# master_jorge3.net
KiCad netlist of a schematic drawn in EAGLE
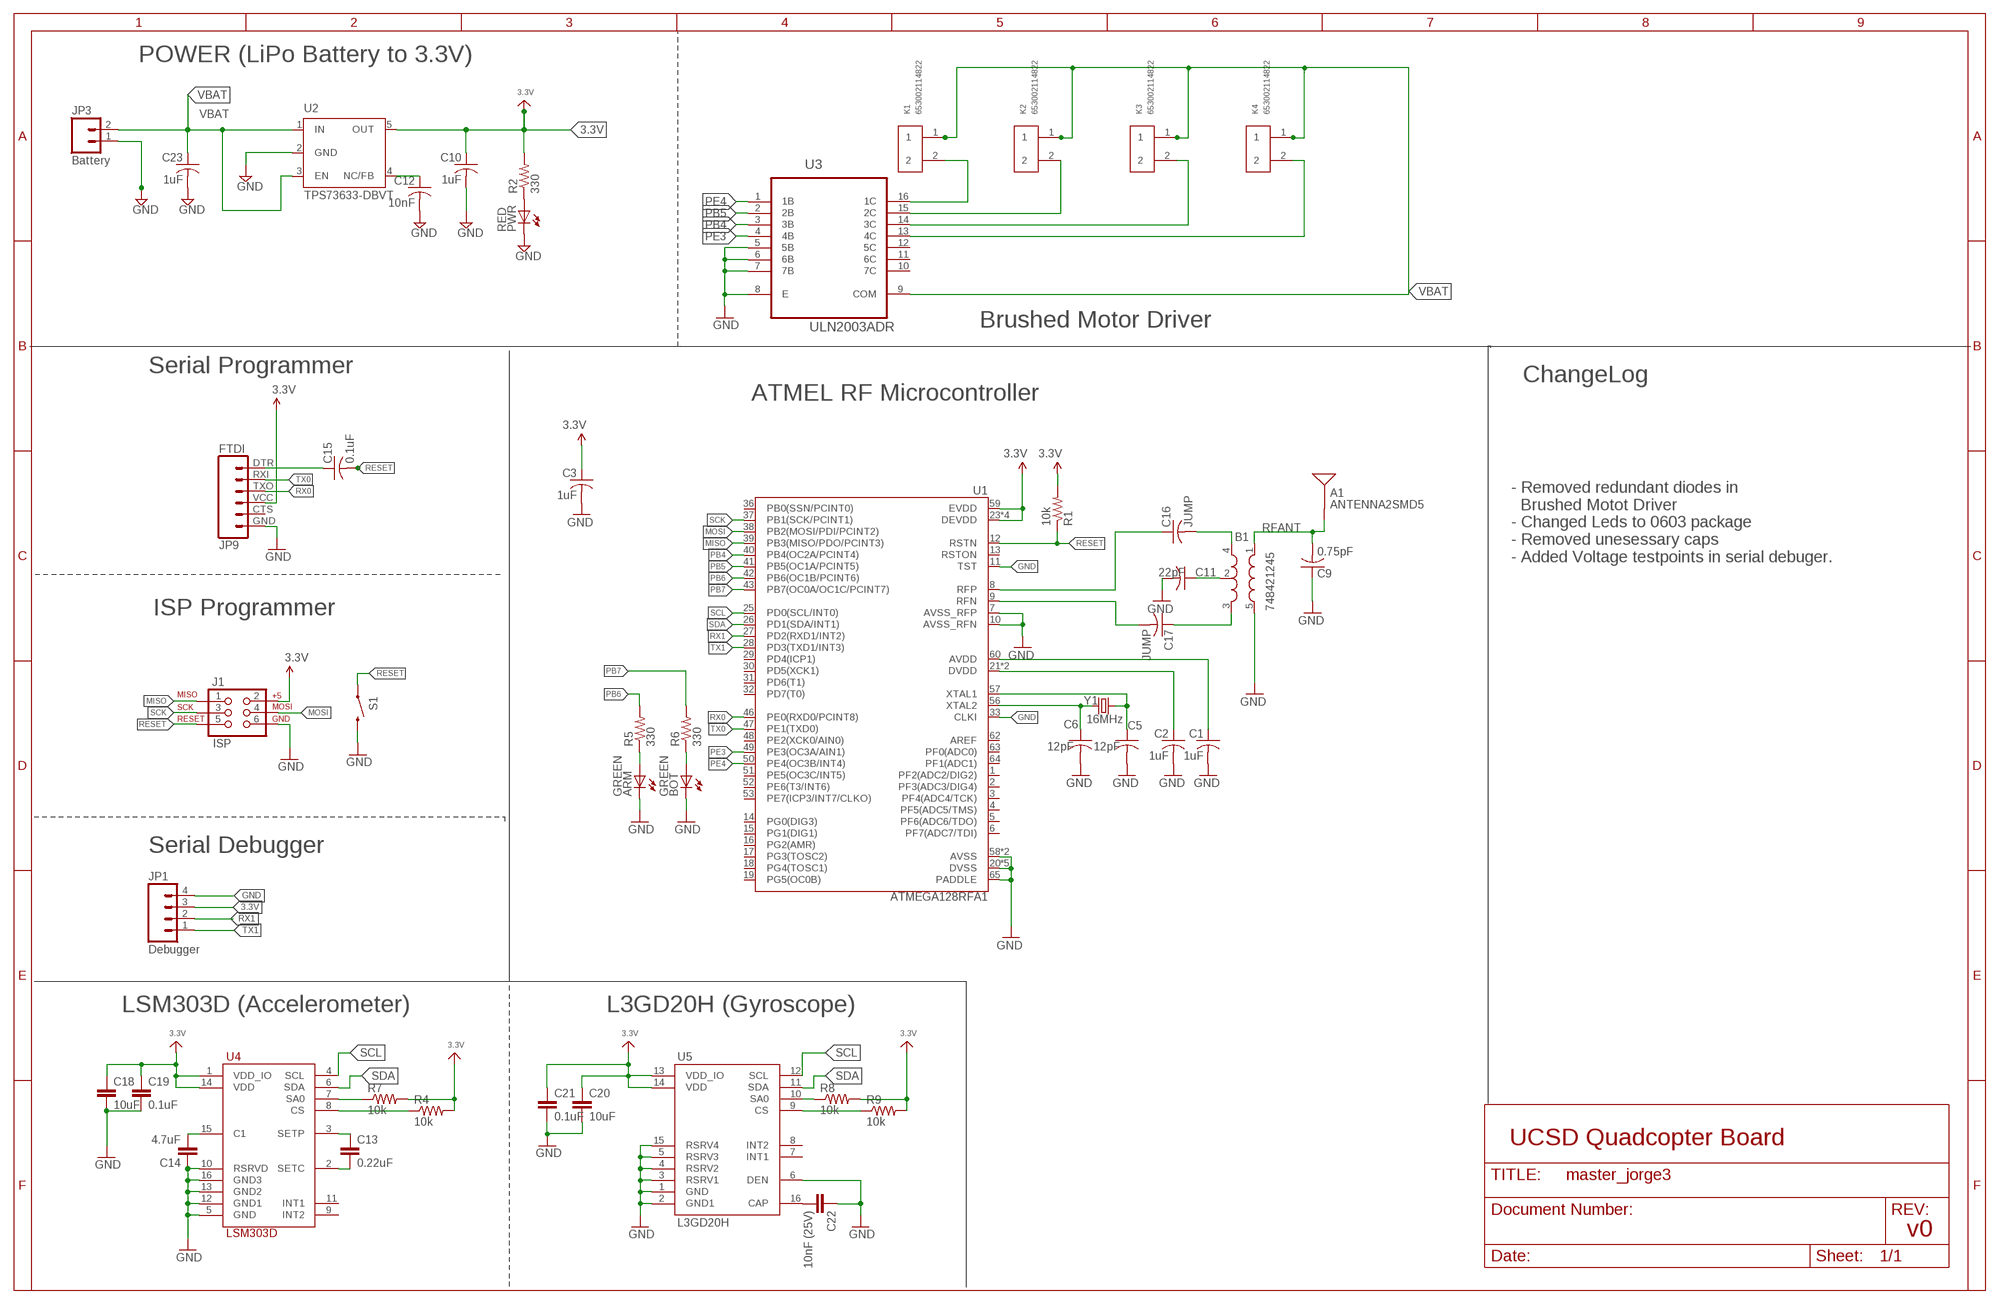
[diagram p0: schematic, sheet 1]

(export (version "E")
  (design (tool "Eeschema 10.0.6"))
  (components
    (comp (ref "A1")
      (value "ANTENNA2SMD5")
      (footprint "eagle-import:ANTENNA-CHIP5")
      (libsource (lib "eagle-import") (part "ANTENNA2SMD5"))
    )
    (comp (ref "ARM")
      (value "GREEN")
      (footprint "eagle-import:CHIP-LED0805")
      (libsource (lib "eagle-import") (part "LEDCHIP-LED0805"))
    )
    (comp (ref "B1")
      (value "748421245")
      (footprint "eagle-import:BALUN")
      (libsource (lib "eagle-import") (part "BALUN0805"))
    )
    (comp (ref "BOT")
      (value "GREEN")
      (footprint "eagle-import:CHIP-LED0805")
      (libsource (lib "eagle-import") (part "LEDCHIP-LED0805"))
    )
    (comp (ref "C1")
      (value "1uF")
      (footprint "eagle-import:C0805")
      (libsource (lib "eagle-import") (part "C-USC0805"))
    )
    (comp (ref "C2")
      (value "1uF")
      (footprint "eagle-import:C0805")
      (libsource (lib "eagle-import") (part "C-USC0805"))
    )
    (comp (ref "C3")
      (value "1uF")
      (footprint "eagle-import:C0805")
      (libsource (lib "eagle-import") (part "C-USC0805"))
    )
    (comp (ref "C5")
      (value "12pF")
      (footprint "eagle-import:C0805")
      (libsource (lib "eagle-import") (part "C-USC0805"))
    )
    (comp (ref "C6")
      (value "12pF")
      (footprint "eagle-import:C0805")
      (libsource (lib "eagle-import") (part "C-USC0805"))
    )
    (comp (ref "C9")
      (value "0.75pF")
      (footprint "eagle-import:C0805")
      (libsource (lib "eagle-import") (part "C-USC0805"))
    )
    (comp (ref "C10")
      (value "1uF")
      (footprint "eagle-import:C0805")
      (libsource (lib "eagle-import") (part "C-USC0805"))
    )
    (comp (ref "C11")
      (value "22pF")
      (footprint "eagle-import:C0805")
      (libsource (lib "eagle-import") (part "C-USC0805"))
    )
    (comp (ref "C12")
      (value "10nF")
      (footprint "eagle-import:C0805")
      (libsource (lib "eagle-import") (part "C-USC0805"))
    )
    (comp (ref "C13")
      (value "0.22uF")
      (footprint "eagle-import:0805")
      (libsource (lib "eagle-import") (part "CAP0805"))
    )
    (comp (ref "C14")
      (value "4.7uF")
      (footprint "eagle-import:0805")
      (libsource (lib "eagle-import") (part "CAP0805"))
    )
    (comp (ref "C15")
      (value "0.1uF")
      (footprint "eagle-import:C0805")
      (libsource (lib "eagle-import") (part "C-USC0805"))
    )
    (comp (ref "C16")
      (value "JUMP")
      (footprint "eagle-import:C0805")
      (libsource (lib "eagle-import") (part "C-USC0805"))
    )
    (comp (ref "C17")
      (value "JUMP")
      (footprint "eagle-import:C0805")
      (libsource (lib "eagle-import") (part "C-USC0805"))
    )
    (comp (ref "C18")
      (value "10uF")
      (footprint "eagle-import:0805")
      (libsource (lib "eagle-import") (part "CAP0805"))
    )
    (comp (ref "C19")
      (value "0.1uF")
      (footprint "eagle-import:0805")
      (libsource (lib "eagle-import") (part "CAP0805"))
    )
    (comp (ref "C20")
      (value "10uF")
      (footprint "eagle-import:0805")
      (libsource (lib "eagle-import") (part "CAP0805"))
    )
    (comp (ref "C21")
      (value "0.1uF")
      (footprint "eagle-import:0805")
      (libsource (lib "eagle-import") (part "CAP0805"))
    )
    (comp (ref "C22")
      (value "10nF (25V)")
      (footprint "eagle-import:0805")
      (libsource (lib "eagle-import") (part "CAP0805"))
    )
    (comp (ref "C23")
      (value "1uF")
      (footprint "eagle-import:C0805")
      (libsource (lib "eagle-import") (part "C-USC0805"))
    )
    (comp (ref "J1")
      (value "ISP")
      (footprint "eagle-import:2X3-NS")
      (libsource (lib "eagle-import") (part "AVR_SPI_PRG_6NS"))
    )
    (comp (ref "JP1")
      (value "Debugger")
      (footprint "eagle-import:1X04")
      (libsource (lib "eagle-import") (part "M04PTH"))
    )
    (comp (ref "JP3")
      (value "Battery")
      (footprint "eagle-import:1X02")
      (libsource (lib "eagle-import") (part "M02PTH"))
    )
    (comp (ref "JP9")
      (value "FTDI")
      (footprint "eagle-import:FTDI_BASIC")
      (libsource (lib "eagle-import") (part "FTDI_BASICPTH"))
    )
    (comp (ref "K1")
      (value "653002114822")
      (footprint "eagle-import:653002114822")
      (libsource (lib "eagle-import") (part "653002114822"))
    )
    (comp (ref "K2")
      (value "653002114822")
      (footprint "eagle-import:653002114822")
      (libsource (lib "eagle-import") (part "653002114822"))
    )
    (comp (ref "K3")
      (value "653002114822")
      (footprint "eagle-import:653002114822")
      (libsource (lib "eagle-import") (part "653002114822"))
    )
    (comp (ref "K4")
      (value "653002114822")
      (footprint "eagle-import:653002114822")
      (libsource (lib "eagle-import") (part "653002114822"))
    )
    (comp (ref "PWR")
      (value "RED")
      (footprint "eagle-import:CHIP-LED0805")
      (libsource (lib "eagle-import") (part "LEDCHIP-LED0805"))
    )
    (comp (ref "R1")
      (value "10k")
      (footprint "eagle-import:R0805")
      (libsource (lib "eagle-import") (part "R-US_R0805"))
    )
    (comp (ref "R2")
      (value "330")
      (footprint "eagle-import:R0805")
      (libsource (lib "eagle-import") (part "R-US_R0805"))
    )
    (comp (ref "R4")
      (value "10k")
      (footprint "eagle-import:0805")
      (libsource (lib "eagle-import") (part "RESISTOR0805-RES"))
    )
    (comp (ref "R5")
      (value "330")
      (footprint "eagle-import:R0805")
      (libsource (lib "eagle-import") (part "R-US_R0805"))
    )
    (comp (ref "R6")
      (value "330")
      (footprint "eagle-import:R0805")
      (libsource (lib "eagle-import") (part "R-US_R0805"))
    )
    (comp (ref "R7")
      (value "10k")
      (footprint "eagle-import:0805")
      (libsource (lib "eagle-import") (part "RESISTOR0805-RES"))
    )
    (comp (ref "R8")
      (value "10k")
      (footprint "eagle-import:0805")
      (libsource (lib "eagle-import") (part "RESISTOR0805-RES"))
    )
    (comp (ref "R9")
      (value "10k")
      (footprint "eagle-import:0805")
      (libsource (lib "eagle-import") (part "RESISTOR0805-RES"))
    )
    (comp (ref "S1")
      (value "SWITCH-MOMENTARY-2SMD")
      (footprint "eagle-import:TACTILE_SWITCH_SMD")
      (libsource (lib "eagle-import") (part "SWITCH-MOMENTARY-2SMD"))
    )
    (comp (ref "U1")
      (value "ATMEGA128RFA1")
      (footprint "eagle-import:QFN-64")
      (libsource (lib "eagle-import") (part "ATMEGA128RFA1"))
    )
    (comp (ref "U2")
      (value "TPS73633-DBVT")
      (footprint "eagle-import:SOT23-DBV")
      (libsource (lib "eagle-import") (part "TPS73633-DBVT"))
    )
    (comp (ref "U3")
      (value "ULN2003ADR")
      (footprint "eagle-import:SOIC127P600X175-16N")
      (libsource (lib "eagle-import") (part "ULN2003ADR"))
    )
    (comp (ref "U4")
      (value "LSM303D")
      (footprint "eagle-import:LGA16_3X3MM")
      (libsource (lib "eagle-import") (part "LSM303D"))
    )
    (comp (ref "U5")
      (value "L3GD20H")
      (footprint "eagle-import:LGA16_3X3MM")
      (libsource (lib "eagle-import") (part "L3GD20H"))
    )
    (comp (ref "Y1")
      (value "16MHz")
      (footprint "eagle-import:CRYSTAL-SMD-5X3")
      (libsource (lib "eagle-import") (part "CRYSTAL5X3"))
    )
  )
  (nets
    (net (code "1") (name "/RFANT") (class "Default")
      (node (ref "A1") (pin "FEED") (pinfunction "SIGNAL_FEED") (pintype "bidirectional"))
      (node (ref "B1") (pin "1") (pinfunction "IN_1") (pintype "bidirectional"))
      (node (ref "C9") (pin "2") (pinfunction "2_2") (pintype "passive"))
    )
    (net (code "2") (name "3.3V") (class "Default")
      (node (ref "C10") (pin "1") (pinfunction "1_1") (pintype "passive"))
      (node (ref "C18") (pin "1") (pinfunction "1_1") (pintype "passive"))
      (node (ref "C19") (pin "1") (pinfunction "1_1") (pintype "passive"))
      (node (ref "C20") (pin "1") (pinfunction "1_1") (pintype "passive"))
      (node (ref "C21") (pin "1") (pinfunction "1_1") (pintype "passive"))
      (node (ref "C3") (pin "1") (pinfunction "1_1") (pintype "passive"))
      (node (ref "J1") (pin "2") (pinfunction "2_2") (pintype "passive"))
      (node (ref "JP1") (pin "3") (pinfunction "3_3") (pintype "passive"))
      (node (ref "JP9") (pin "VCC") (pinfunction "4_VCC") (pintype "passive"))
      (node (ref "R1") (pin "2") (pinfunction "2_2") (pintype "passive"))
      (node (ref "R2") (pin "2") (pinfunction "2_2") (pintype "passive"))
      (node (ref "R4") (pin "2") (pinfunction "2_2") (pintype "passive"))
      (node (ref "R7") (pin "2") (pinfunction "2_2") (pintype "passive"))
      (node (ref "R8") (pin "2") (pinfunction "2_2") (pintype "passive"))
      (node (ref "R9") (pin "2") (pinfunction "2_2") (pintype "passive"))
      (node (ref "U1") (pin "23") (pinfunction "DEVDD_23") (pintype "bidirectional"))
      (node (ref "U1") (pin "34") (pinfunction "DEVDD_34") (pintype "bidirectional"))
      (node (ref "U1") (pin "44") (pinfunction "DEVDD_44") (pintype "bidirectional"))
      (node (ref "U1") (pin "54") (pinfunction "DEVDD_54") (pintype "bidirectional"))
      (node (ref "U1") (pin "59") (pinfunction "EVDD_59") (pintype "bidirectional"))
      (node (ref "U2") (pin "5") (pinfunction "OUT_5") (pintype "passive"))
      (node (ref "U4") (pin "1") (pinfunction "VDD_IO_1") (pintype "bidirectional"))
      (node (ref "U4") (pin "14") (pinfunction "VDD_14") (pintype "bidirectional"))
      (node (ref "U5") (pin "13") (pinfunction "VDD_IO_13") (pintype "bidirectional"))
      (node (ref "U5") (pin "14") (pinfunction "VDD_14") (pintype "bidirectional"))
    )
    (net (code "3") (name "GND") (class "Default")
      (node (ref "ARM") (pin "C") (pinfunction "C_C") (pintype "passive"))
      (node (ref "B1") (pin "5") (pinfunction "GND_5") (pintype "bidirectional"))
      (node (ref "BOT") (pin "C") (pinfunction "C_C") (pintype "passive"))
      (node (ref "C1") (pin "2") (pinfunction "2_2") (pintype "passive"))
      (node (ref "C10") (pin "2") (pinfunction "2_2") (pintype "passive"))
      (node (ref "C11") (pin "2") (pinfunction "2_2") (pintype "passive"))
      (node (ref "C12") (pin "2") (pinfunction "2_2") (pintype "passive"))
      (node (ref "C14") (pin "1") (pinfunction "1_1") (pintype "passive"))
      (node (ref "C18") (pin "2") (pinfunction "2_2") (pintype "passive"))
      (node (ref "C19") (pin "2") (pinfunction "2_2") (pintype "passive"))
      (node (ref "C2") (pin "2") (pinfunction "2_2") (pintype "passive"))
      (node (ref "C20") (pin "2") (pinfunction "2_2") (pintype "passive"))
      (node (ref "C21") (pin "2") (pinfunction "2_2") (pintype "passive"))
      (node (ref "C22") (pin "1") (pinfunction "1_1") (pintype "passive"))
      (node (ref "C23") (pin "2") (pinfunction "2_2") (pintype "passive"))
      (node (ref "C3") (pin "2") (pinfunction "2_2") (pintype "passive"))
      (node (ref "C5") (pin "2") (pinfunction "2_2") (pintype "passive"))
      (node (ref "C6") (pin "2") (pinfunction "2_2") (pintype "passive"))
      (node (ref "C9") (pin "1") (pinfunction "1_1") (pintype "passive"))
      (node (ref "J1") (pin "6") (pinfunction "6_6") (pintype "passive"))
      (node (ref "JP1") (pin "4") (pinfunction "4_4") (pintype "passive"))
      (node (ref "JP3") (pin "1") (pinfunction "1_1") (pintype "passive"))
      (node (ref "JP9") (pin "GND") (pinfunction "6_GND") (pintype "passive"))
      (node (ref "PWR") (pin "C") (pinfunction "C_C") (pintype "passive"))
      (node (ref "S1") (pin "3") (pinfunction "2_3") (pintype "passive"))
      (node (ref "U1") (pin "10") (pinfunction "AVSS_RFN_10") (pintype "bidirectional"))
      (node (ref "U1") (pin "11") (pinfunction "TST_11") (pintype "bidirectional"))
      (node (ref "U1") (pin "20") (pinfunction "DVSS_20") (pintype "bidirectional"))
      (node (ref "U1") (pin "24") (pinfunction "DVSS_24") (pintype "bidirectional"))
      (node (ref "U1") (pin "33") (pinfunction "CLKI_33") (pintype "bidirectional"))
      (node (ref "U1") (pin "35") (pinfunction "DVSS_35") (pintype "bidirectional"))
      (node (ref "U1") (pin "45") (pinfunction "DVSS_45") (pintype "bidirectional"))
      (node (ref "U1") (pin "55") (pinfunction "DVSS_55") (pintype "bidirectional"))
      (node (ref "U1") (pin "58") (pinfunction "AVSS_58") (pintype "bidirectional"))
      (node (ref "U1") (pin "61") (pinfunction "AVSS_61") (pintype "bidirectional"))
      (node (ref "U1") (pin "65") (pinfunction "PADDLE_65") (pintype "bidirectional"))
      (node (ref "U1") (pin "7") (pinfunction "AVSS_RFP_7") (pintype "bidirectional"))
      (node (ref "U2") (pin "2") (pinfunction "GND_2") (pintype "input"))
      (node (ref "U3") (pin "5") (pinfunction "5B_5") (pintype "input"))
      (node (ref "U3") (pin "6") (pinfunction "6B_6") (pintype "input"))
      (node (ref "U3") (pin "7") (pinfunction "7B_7") (pintype "input"))
      (node (ref "U3") (pin "8") (pinfunction "E_8") (pintype "input"))
      (node (ref "U4") (pin "10") (pinfunction "RSRVD_10") (pintype "bidirectional"))
      (node (ref "U4") (pin "12") (pinfunction "GND1_12") (pintype "bidirectional"))
      (node (ref "U4") (pin "13") (pinfunction "GND2_13") (pintype "bidirectional"))
      (node (ref "U4") (pin "16") (pinfunction "GND3_16") (pintype "bidirectional"))
      (node (ref "U4") (pin "5") (pinfunction "GND_5") (pintype "bidirectional"))
      (node (ref "U5") (pin "1") (pinfunction "GND_1") (pintype "bidirectional"))
      (node (ref "U5") (pin "15") (pinfunction "RSRV4_15") (pintype "bidirectional"))
      (node (ref "U5") (pin "2") (pinfunction "GND1_2") (pintype "bidirectional"))
      (node (ref "U5") (pin "3") (pinfunction "RSRV1_3") (pintype "bidirectional"))
      (node (ref "U5") (pin "4") (pinfunction "RSRV2_4") (pintype "bidirectional"))
      (node (ref "U5") (pin "5") (pinfunction "RSRV3_5") (pintype "bidirectional"))
      (node (ref "U5") (pin "6") (pinfunction "DEN_6") (pintype "bidirectional"))
    )
    (net (code "4") (name "MISO") (class "Default")
      (node (ref "J1") (pin "1") (pinfunction "1_1") (pintype "passive"))
      (node (ref "U1") (pin "39") (pinfunction "PB3(MISO/PDO/PCINT3)_39") (pintype "bidirectional"))
    )
    (net (code "5") (name "MOSI") (class "Default")
      (node (ref "J1") (pin "4") (pinfunction "4_4") (pintype "passive"))
      (node (ref "U1") (pin "38") (pinfunction "PB2(MOSI/PDI/PCINT2)_38") (pintype "bidirectional"))
    )
    (net (code "6") (name "Net-(ARM-PadA)") (class "Default")
      (node (ref "ARM") (pin "A") (pinfunction "A_A") (pintype "passive"))
      (node (ref "R5") (pin "1") (pinfunction "1_1") (pintype "passive"))
    )
    (net (code "7") (name "Net-(B1-GND-Pad2)") (class "Default")
      (node (ref "B1") (pin "2") (pinfunction "GND_2") (pintype "bidirectional"))
      (node (ref "C11") (pin "1") (pinfunction "1_1") (pintype "passive"))
    )
    (net (code "8") (name "Net-(B1-OUT1)") (class "Default")
      (node (ref "B1") (pin "4") (pinfunction "OUT1_4") (pintype "bidirectional"))
      (node (ref "C16") (pin "2") (pinfunction "2_2") (pintype "passive"))
    )
    (net (code "9") (name "Net-(B1-OUT2)") (class "Default")
      (node (ref "B1") (pin "3") (pinfunction "OUT2_3") (pintype "bidirectional"))
      (node (ref "C17") (pin "1") (pinfunction "1_1") (pintype "passive"))
    )
    (net (code "10") (name "Net-(BOT-PadA)") (class "Default")
      (node (ref "BOT") (pin "A") (pinfunction "A_A") (pintype "passive"))
      (node (ref "R6") (pin "1") (pinfunction "1_1") (pintype "passive"))
    )
    (net (code "11") (name "Net-(C2-Pad1)") (class "Default")
      (node (ref "C2") (pin "1") (pinfunction "1_1") (pintype "passive"))
      (node (ref "U1") (pin "21") (pinfunction "DVDD_21") (pintype "bidirectional"))
      (node (ref "U1") (pin "22") (pinfunction "DVDD_22") (pintype "bidirectional"))
    )
    (net (code "12") (name "Net-(JP9-1)") (class "Default")
      (node (ref "C15") (pin "1") (pinfunction "1_1") (pintype "passive"))
      (node (ref "JP9") (pin "DTR") (pinfunction "1_DTR") (pintype "passive"))
    )
    (net (code "13") (name "Net-(PWR-PadA)") (class "Default")
      (node (ref "PWR") (pin "A") (pinfunction "A_A") (pintype "passive"))
      (node (ref "R2") (pin "1") (pinfunction "1_1") (pintype "passive"))
    )
    (net (code "14") (name "Net-(U1-AVDD)") (class "Default")
      (node (ref "C1") (pin "1") (pinfunction "1_1") (pintype "passive"))
      (node (ref "U1") (pin "60") (pinfunction "AVDD_60") (pintype "bidirectional"))
    )
    (net (code "15") (name "Net-(U1-RFN)") (class "Default")
      (node (ref "C17") (pin "2") (pinfunction "2_2") (pintype "passive"))
      (node (ref "U1") (pin "9") (pinfunction "RFN_9") (pintype "bidirectional"))
    )
    (net (code "16") (name "Net-(U1-RFP)") (class "Default")
      (node (ref "C16") (pin "1") (pinfunction "1_1") (pintype "passive"))
      (node (ref "U1") (pin "8") (pinfunction "RFP_8") (pintype "bidirectional"))
    )
    (net (code "17") (name "Net-(U1-XTAL1)") (class "Default")
      (node (ref "C5") (pin "1") (pinfunction "1_1") (pintype "passive"))
      (node (ref "U1") (pin "57") (pinfunction "XTAL1_57") (pintype "bidirectional"))
      (node (ref "Y1") (pin "3") (pinfunction "2_3") (pintype "passive"))
    )
    (net (code "18") (name "Net-(U1-XTAL2)") (class "Default")
      (node (ref "C6") (pin "1") (pinfunction "1_1") (pintype "passive"))
      (node (ref "U1") (pin "56") (pinfunction "XTAL2_56") (pintype "bidirectional"))
      (node (ref "Y1") (pin "1") (pinfunction "1_1") (pintype "passive"))
    )
    (net (code "19") (name "Net-(U2-NC{slash}FB)") (class "Default")
      (node (ref "C12") (pin "1") (pinfunction "1_1") (pintype "passive"))
      (node (ref "U2") (pin "4") (pinfunction "NC/FB_4") (pintype "passive"))
    )
    (net (code "20") (name "Net-(U3-1C)") (class "Default")
      (node (ref "K1") (pin "2") (pinfunction "2_2") (pintype "bidirectional"))
      (node (ref "U3") (pin "16") (pinfunction "1C_16") (pintype "output"))
    )
    (net (code "21") (name "Net-(U3-2C)") (class "Default")
      (node (ref "K2") (pin "2") (pinfunction "2_2") (pintype "bidirectional"))
      (node (ref "U3") (pin "15") (pinfunction "2C_15") (pintype "output"))
    )
    (net (code "22") (name "Net-(U3-3C)") (class "Default")
      (node (ref "K3") (pin "2") (pinfunction "2_2") (pintype "bidirectional"))
      (node (ref "U3") (pin "14") (pinfunction "3C_14") (pintype "output"))
    )
    (net (code "23") (name "Net-(U3-4C)") (class "Default")
      (node (ref "K4") (pin "2") (pinfunction "2_2") (pintype "bidirectional"))
      (node (ref "U3") (pin "13") (pinfunction "4C_13") (pintype "output"))
    )
    (net (code "24") (name "Net-(U4-C1)") (class "Default")
      (node (ref "C14") (pin "2") (pinfunction "2_2") (pintype "passive"))
      (node (ref "U4") (pin "15") (pinfunction "C1_15") (pintype "bidirectional"))
    )
    (net (code "25") (name "Net-(U4-CS)") (class "Default")
      (node (ref "R4") (pin "1") (pinfunction "1_1") (pintype "passive"))
      (node (ref "U4") (pin "8") (pinfunction "CS_8") (pintype "bidirectional"))
    )
    (net (code "26") (name "Net-(U4-SA0)") (class "Default")
      (node (ref "R7") (pin "1") (pinfunction "1_1") (pintype "passive"))
      (node (ref "U4") (pin "7") (pinfunction "SA0_7") (pintype "bidirectional"))
    )
    (net (code "27") (name "Net-(U4-SETC)") (class "Default")
      (node (ref "C13") (pin "2") (pinfunction "2_2") (pintype "passive"))
      (node (ref "U4") (pin "2") (pinfunction "SETC_2") (pintype "bidirectional"))
    )
    (net (code "28") (name "Net-(U4-SETP)") (class "Default")
      (node (ref "C13") (pin "1") (pinfunction "1_1") (pintype "passive"))
      (node (ref "U4") (pin "3") (pinfunction "SETP_3") (pintype "bidirectional"))
    )
    (net (code "29") (name "Net-(U5-CAP)") (class "Default")
      (node (ref "C22") (pin "2") (pinfunction "2_2") (pintype "passive"))
      (node (ref "U5") (pin "16") (pinfunction "CAP_16") (pintype "bidirectional"))
    )
    (net (code "30") (name "Net-(U5-CS)") (class "Default")
      (node (ref "R9") (pin "1") (pinfunction "1_1") (pintype "passive"))
      (node (ref "U5") (pin "9") (pinfunction "CS_9") (pintype "bidirectional"))
    )
    (net (code "31") (name "Net-(U5-SA0)") (class "Default")
      (node (ref "R8") (pin "1") (pinfunction "1_1") (pintype "passive"))
      (node (ref "U5") (pin "10") (pinfunction "SA0_10") (pintype "bidirectional"))
    )
    (net (code "32") (name "PB4") (class "Default")
      (node (ref "U1") (pin "40") (pinfunction "PB4(OC2A/PCINT4)_40") (pintype "bidirectional"))
      (node (ref "U3") (pin "3") (pinfunction "3B_3") (pintype "input"))
    )
    (net (code "33") (name "PB5") (class "Default")
      (node (ref "U1") (pin "41") (pinfunction "PB5(OC1A/PCINT5)_41") (pintype "bidirectional"))
      (node (ref "U3") (pin "2") (pinfunction "2B_2") (pintype "input"))
    )
    (net (code "34") (name "PB6") (class "Default")
      (node (ref "R5") (pin "2") (pinfunction "2_2") (pintype "passive"))
      (node (ref "U1") (pin "42") (pinfunction "PB6(OC1B/PCINT6)_42") (pintype "bidirectional"))
    )
    (net (code "35") (name "PB7") (class "Default")
      (node (ref "R6") (pin "2") (pinfunction "2_2") (pintype "passive"))
      (node (ref "U1") (pin "43") (pinfunction "PB7(OC0A/OC1C/PCINT7)_43") (pintype "bidirectional"))
    )
    (net (code "36") (name "PE3") (class "Default")
      (node (ref "U1") (pin "49") (pinfunction "PE3(OC3A/AIN1)_49") (pintype "bidirectional"))
      (node (ref "U3") (pin "4") (pinfunction "4B_4") (pintype "input"))
    )
    (net (code "37") (name "PE4") (class "Default")
      (node (ref "U1") (pin "50") (pinfunction "PE4(OC3B/INT4)_50") (pintype "bidirectional"))
      (node (ref "U3") (pin "1") (pinfunction "1B_1") (pintype "input"))
    )
    (net (code "38") (name "RESET") (class "Default")
      (node (ref "C15") (pin "2") (pinfunction "2_2") (pintype "passive"))
      (node (ref "J1") (pin "5") (pinfunction "5_5") (pintype "passive"))
      (node (ref "R1") (pin "1") (pinfunction "1_1") (pintype "passive"))
      (node (ref "S1") (pin "1") (pinfunction "1_1") (pintype "passive"))
      (node (ref "U1") (pin "12") (pinfunction "RSTN_12") (pintype "bidirectional"))
    )
    (net (code "39") (name "RX0") (class "Default")
      (node (ref "JP9") (pin "TXO") (pinfunction "3_TXO") (pintype "passive"))
      (node (ref "U1") (pin "46") (pinfunction "PE0(RXD0/PCINT8)_46") (pintype "bidirectional"))
    )
    (net (code "40") (name "RX1") (class "Default")
      (node (ref "JP1") (pin "2") (pinfunction "2_2") (pintype "passive"))
      (node (ref "U1") (pin "27") (pinfunction "PD2(RXD1/INT2)_27") (pintype "bidirectional"))
    )
    (net (code "41") (name "SCK") (class "Default")
      (node (ref "J1") (pin "3") (pinfunction "3_3") (pintype "passive"))
      (node (ref "U1") (pin "37") (pinfunction "PB1(SCK/PCINT1)_37") (pintype "bidirectional"))
    )
    (net (code "42") (name "SCL") (class "Default")
      (node (ref "U1") (pin "25") (pinfunction "PD0(SCL/INT0)_25") (pintype "bidirectional"))
      (node (ref "U4") (pin "4") (pinfunction "SCL_4") (pintype "bidirectional"))
      (node (ref "U5") (pin "12") (pinfunction "SCL_12") (pintype "bidirectional"))
    )
    (net (code "43") (name "SDA") (class "Default")
      (node (ref "U1") (pin "26") (pinfunction "PD1(SDA/INT1)_26") (pintype "bidirectional"))
      (node (ref "U4") (pin "6") (pinfunction "SDA_6") (pintype "bidirectional"))
      (node (ref "U5") (pin "11") (pinfunction "SDA_11") (pintype "bidirectional"))
    )
    (net (code "44") (name "TX0") (class "Default")
      (node (ref "JP9") (pin "RXI") (pinfunction "2_RXI") (pintype "passive"))
      (node (ref "U1") (pin "47") (pinfunction "PE1(TXD0)_47") (pintype "bidirectional"))
    )
    (net (code "45") (name "TX1") (class "Default")
      (node (ref "JP1") (pin "1") (pinfunction "1_1") (pintype "passive"))
      (node (ref "U1") (pin "28") (pinfunction "PD3(TXD1/INT3)_28") (pintype "bidirectional"))
    )
    (net (code "46") (name "VBAT") (class "Default")
      (node (ref "C23") (pin "1") (pinfunction "1_1") (pintype "passive"))
      (node (ref "JP3") (pin "2") (pinfunction "2_2") (pintype "passive"))
      (node (ref "K1") (pin "1") (pinfunction "1_1") (pintype "bidirectional"))
      (node (ref "K2") (pin "1") (pinfunction "1_1") (pintype "bidirectional"))
      (node (ref "K3") (pin "1") (pinfunction "1_1") (pintype "bidirectional"))
      (node (ref "K4") (pin "1") (pinfunction "1_1") (pintype "bidirectional"))
      (node (ref "U2") (pin "1") (pinfunction "IN_1") (pintype "input"))
      (node (ref "U2") (pin "3") (pinfunction "EN_3") (pintype "power_in"))
      (node (ref "U3") (pin "9") (pinfunction "COM_9") (pintype "output"))
    )
    (net (code "47") (name "unconnected-(JP9-5-PadCTS)") (class "Default")
      (node (ref "JP9") (pin "CTS") (pinfunction "5_CTS") (pintype "passive"))
    )
    (net (code "48") (name "unconnected-(U1-AREF-Pad62)") (class "Default")
      (node (ref "U1") (pin "62") (pinfunction "AREF_62") (pintype "bidirectional"))
    )
    (net (code "49") (name "unconnected-(U1-PB0(SSN{slash}PCINT0)-Pad36)") (class "Default")
      (node (ref "U1") (pin "36") (pinfunction "PB0(SSN/PCINT0)_36") (pintype "bidirectional"))
    )
    (net (code "50") (name "unconnected-(U1-PD4(ICP1)-Pad29)") (class "Default")
      (node (ref "U1") (pin "29") (pinfunction "PD4(ICP1)_29") (pintype "bidirectional"))
    )
    (net (code "51") (name "unconnected-(U1-PD5(XCK1)-Pad30)") (class "Default")
      (node (ref "U1") (pin "30") (pinfunction "PD5(XCK1)_30") (pintype "bidirectional"))
    )
    (net (code "52") (name "unconnected-(U1-PD6(T1)-Pad31)") (class "Default")
      (node (ref "U1") (pin "31") (pinfunction "PD6(T1)_31") (pintype "bidirectional"))
    )
    (net (code "53") (name "unconnected-(U1-PD7(T0)-Pad32)") (class "Default")
      (node (ref "U1") (pin "32") (pinfunction "PD7(T0)_32") (pintype "bidirectional"))
    )
    (net (code "54") (name "unconnected-(U1-PE2(XCK0{slash}AIN0)-Pad48)") (class "Default")
      (node (ref "U1") (pin "48") (pinfunction "PE2(XCK0/AIN0)_48") (pintype "bidirectional"))
    )
    (net (code "55") (name "unconnected-(U1-PE5(OC3C{slash}INT5)-Pad51)") (class "Default")
      (node (ref "U1") (pin "51") (pinfunction "PE5(OC3C/INT5)_51") (pintype "bidirectional"))
    )
    (net (code "56") (name "unconnected-(U1-PE6(T3{slash}INT6)-Pad52)") (class "Default")
      (node (ref "U1") (pin "52") (pinfunction "PE6(T3/INT6)_52") (pintype "bidirectional"))
    )
    (net (code "57") (name "unconnected-(U1-PE7(ICP3{slash}INT7{slash}CLKO)-Pad53)") (class "Default")
      (node (ref "U1") (pin "53") (pinfunction "PE7(ICP3/INT7/CLKO)_53") (pintype "bidirectional"))
    )
    (net (code "58") (name "unconnected-(U1-PF0(ADC0)-Pad63)") (class "Default")
      (node (ref "U1") (pin "63") (pinfunction "PF0(ADC0)_63") (pintype "bidirectional"))
    )
    (net (code "59") (name "unconnected-(U1-PF1(ADC1)-Pad64)") (class "Default")
      (node (ref "U1") (pin "64") (pinfunction "PF1(ADC1)_64") (pintype "bidirectional"))
    )
    (net (code "60") (name "unconnected-(U1-PF2(ADC2{slash}DIG2)-Pad1)") (class "Default")
      (node (ref "U1") (pin "1") (pinfunction "PF2(ADC2/DIG2)_1") (pintype "bidirectional"))
    )
    (net (code "61") (name "unconnected-(U1-PF3(ADC3{slash}DIG4)-Pad2)") (class "Default")
      (node (ref "U1") (pin "2") (pinfunction "PF3(ADC3/DIG4)_2") (pintype "bidirectional"))
    )
    (net (code "62") (name "unconnected-(U1-PF4(ADC4{slash}TCK)-Pad3)") (class "Default")
      (node (ref "U1") (pin "3") (pinfunction "PF4(ADC4/TCK)_3") (pintype "bidirectional"))
    )
    (net (code "63") (name "unconnected-(U1-PF5(ADC5{slash}TMS)-Pad4)") (class "Default")
      (node (ref "U1") (pin "4") (pinfunction "PF5(ADC5/TMS)_4") (pintype "bidirectional"))
    )
    (net (code "64") (name "unconnected-(U1-PF6(ADC6{slash}TDO)-Pad5)") (class "Default")
      (node (ref "U1") (pin "5") (pinfunction "PF6(ADC6/TDO)_5") (pintype "bidirectional"))
    )
    (net (code "65") (name "unconnected-(U1-PF7(ADC7{slash}TDI)-Pad6)") (class "Default")
      (node (ref "U1") (pin "6") (pinfunction "PF7(ADC7/TDI)_6") (pintype "bidirectional"))
    )
    (net (code "66") (name "unconnected-(U1-PG0(DIG3)-Pad14)") (class "Default")
      (node (ref "U1") (pin "14") (pinfunction "PG0(DIG3)_14") (pintype "bidirectional"))
    )
    (net (code "67") (name "unconnected-(U1-PG1(DIG1)-Pad15)") (class "Default")
      (node (ref "U1") (pin "15") (pinfunction "PG1(DIG1)_15") (pintype "bidirectional"))
    )
    (net (code "68") (name "unconnected-(U1-PG2(AMR)-Pad16)") (class "Default")
      (node (ref "U1") (pin "16") (pinfunction "PG2(AMR)_16") (pintype "bidirectional"))
    )
    (net (code "69") (name "unconnected-(U1-PG3(TOSC2)-Pad17)") (class "Default")
      (node (ref "U1") (pin "17") (pinfunction "PG3(TOSC2)_17") (pintype "bidirectional"))
    )
    (net (code "70") (name "unconnected-(U1-PG4(TOSC1)-Pad18)") (class "Default")
      (node (ref "U1") (pin "18") (pinfunction "PG4(TOSC1)_18") (pintype "bidirectional"))
    )
    (net (code "71") (name "unconnected-(U1-PG5(OC0B)-Pad19)") (class "Default")
      (node (ref "U1") (pin "19") (pinfunction "PG5(OC0B)_19") (pintype "bidirectional"))
    )
    (net (code "72") (name "unconnected-(U1-RSTON-Pad13)") (class "Default")
      (node (ref "U1") (pin "13") (pinfunction "RSTON_13") (pintype "bidirectional"))
    )
    (net (code "73") (name "unconnected-(U3-5C-Pad12)") (class "Default")
      (node (ref "U3") (pin "12") (pinfunction "5C_12") (pintype "output"))
    )
    (net (code "74") (name "unconnected-(U3-6C-Pad11)") (class "Default")
      (node (ref "U3") (pin "11") (pinfunction "6C_11") (pintype "output"))
    )
    (net (code "75") (name "unconnected-(U3-7C-Pad10)") (class "Default")
      (node (ref "U3") (pin "10") (pinfunction "7C_10") (pintype "output"))
    )
    (net (code "76") (name "unconnected-(U4-INT1-Pad11)") (class "Default")
      (node (ref "U4") (pin "11") (pinfunction "INT1_11") (pintype "bidirectional"))
    )
    (net (code "77") (name "unconnected-(U4-INT2-Pad9)") (class "Default")
      (node (ref "U4") (pin "9") (pinfunction "INT2_9") (pintype "bidirectional"))
    )
    (net (code "78") (name "unconnected-(U5-INT1-Pad7)") (class "Default")
      (node (ref "U5") (pin "7") (pinfunction "INT1_7") (pintype "bidirectional"))
    )
    (net (code "79") (name "unconnected-(U5-INT2-Pad8)") (class "Default")
      (node (ref "U5") (pin "8") (pinfunction "INT2_8") (pintype "bidirectional"))
    )
  )
)
